# ESP32Board_V1.net
KiCad netlist of a schematic drawn in EAGLE
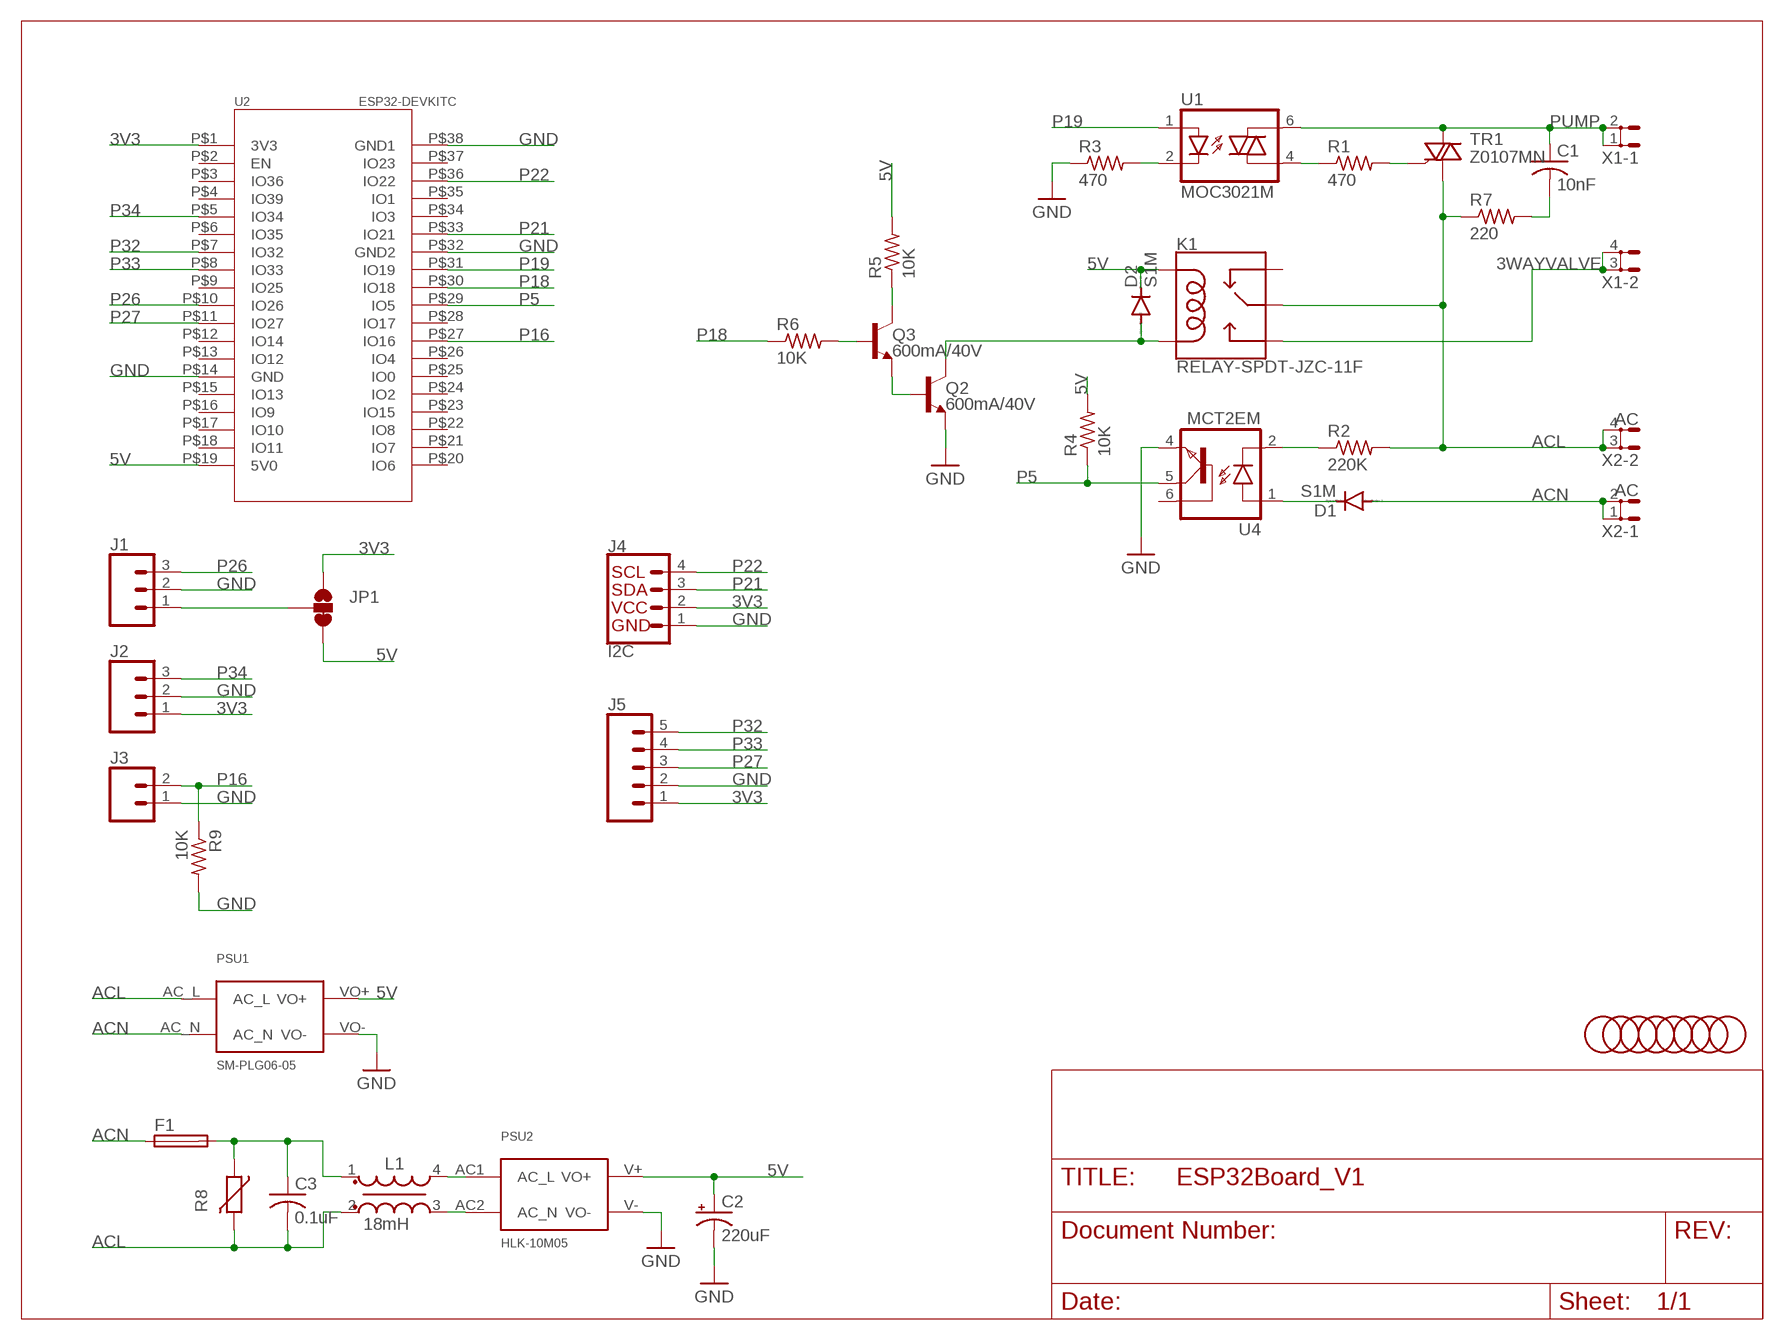
[diagram p0: schematic, sheet 1]

(export (version "E")
  (design (tool "Eeschema 10.0.6"))
  (components
    (comp (ref "C1")
      (value "10nF")
      (footprint "eagle-import:C075-032X103")
      (fields (field (name "BOM_SUPPLIERPART") "C506848"))
      (libsource (lib "eagle-import") (part "C-US075-032X103"))
    )
    (comp (ref "C2")
      (value "220uF")
      (footprint "eagle-import:E2,5-6")
      (libsource (lib "eagle-import") (part "CPOL-USE2.5-6"))
    )
    (comp (ref "C3")
      (value "0.1uF")
      (footprint "eagle-import:C150-054X183")
      (libsource (lib "eagle-import") (part "C-US150-054X183"))
    )
    (comp (ref "D1")
      (value "S1M")
      (footprint "eagle-import:SMA")
      (fields (field (name "BOM_SUPPLIERPART") "C232826"))
      (libsource (lib "eagle-import") (part "S1M"))
    )
    (comp (ref "D2")
      (value "S1M")
      (footprint "eagle-import:SMA")
      (fields (field (name "BOM_SUPPLIERPART") "C232826"))
      (libsource (lib "eagle-import") (part "S1M"))
    )
    (comp (ref "F1")
      (value "FUSETE5")
      (footprint "eagle-import:TE5")
      (libsource (lib "eagle-import") (part "FUSETE5"))
    )
    (comp (ref "J1")
      (value "CONN_03JST-PTH")
      (footprint "eagle-import:JST-3-PTH")
      (fields (field (name "BOM_SUPPLIERPART") "C157929"))
      (libsource (lib "eagle-import") (part "CONN_03JST-PTH"))
    )
    (comp (ref "J2")
      (value "CONN_03JST-PTH")
      (footprint "eagle-import:JST-3-PTH")
      (fields (field (name "BOM_SUPPLIERPART") "C157929"))
      (libsource (lib "eagle-import") (part "CONN_03JST-PTH"))
    )
    (comp (ref "J3")
      (value "CONN_02JST-PTH-2")
      (footprint "eagle-import:JST-2-PTH")
      (fields (field (name "BOM_SUPPLIERPART") "C173752"))
      (libsource (lib "eagle-import") (part "CONN_02JST-PTH-2"))
    )
    (comp (ref "J4")
      (value "I2C")
      (footprint "eagle-import:JST04_1MM_VERT")
      (fields (field (name "BOM_SUPPLIERPART") "C160390"))
      (libsource (lib "eagle-import") (part "QWIIC_CONNECTOR"))
    )
    (comp (ref "J5")
      (value "CONN_05JST")
      (footprint "eagle-import:JST-5-PTH")
      (fields (field (name "BOM_SUPPLIERPART") "C157923"))
      (libsource (lib "eagle-import") (part "CONN_05JST"))
    )
    (comp (ref "JP1")
      (value "JUMPER-SMT_3_1-NC_TRACE_SILK")
      (footprint "eagle-import:SMT-JUMPER_3_1-NC_TRACE_SILK")
      (libsource (lib "eagle-import") (part "JUMPER-SMT_3_1-NC_TRACE_SILK"))
    )
    (comp (ref "K1")
      (value "RELAY-SPDT-JZC-11F")
      (footprint "eagle-import:RELAY-JZC")
      (fields (field (name "BOM_SUPPLIERPART") "C355393"))
      (libsource (lib "eagle-import") (part "RELAY-SPDT-JZC-11F"))
    )
    (comp (ref "L1")
      (value "18mH")
      (footprint "eagle-import:WE-TFC_UU9.8V")
      (libsource (lib "eagle-import") (part "WE-TFC_UU9.8V_744862180"))
    )
    (comp (ref "PSU1")
      (value "SM-PLG06-05")
      (footprint "eagle-import:SM-PLG06")
      (libsource (lib "eagle-import") (part "SM-PLG06-05"))
    )
    (comp (ref "PSU2")
      (value "HLK-10M05")
      (footprint "eagle-import:HLK-10MXX")
      (libsource (lib "eagle-import") (part "HLK-10M05"))
    )
    (comp (ref "Q2")
      (value "600mA/40V")
      (footprint "eagle-import:SOT23-3")
      (fields (field (name "BOM_SUPPLIERPART") "C164886"))
      (libsource (lib "eagle-import") (part "TRANS_NPN-MMBT2222AL"))
    )
    (comp (ref "Q3")
      (value "600mA/40V")
      (footprint "eagle-import:SOT23-3")
      (fields (field (name "BOM_SUPPLIERPART") "C164886"))
      (libsource (lib "eagle-import") (part "TRANS_NPN-MMBT2222AL"))
    )
    (comp (ref "R1")
      (value "470")
      (footprint "eagle-import:R0603")
      (fields (field (name "BOM_SUPPLIERPART") "C328361"))
      (libsource (lib "eagle-import") (part "R-US_R0603"))
    )
    (comp (ref "R2")
      (value "220K")
      (footprint "eagle-import:R0603")
      (fields (field (name "BOM_SUPPLIERPART") "C217882"))
      (libsource (lib "eagle-import") (part "R-US_R0603"))
    )
    (comp (ref "R3")
      (value "470")
      (footprint "eagle-import:R0603")
      (fields (field (name "BOM_SUPPLIERPART") "C328361"))
      (libsource (lib "eagle-import") (part "R-US_R0603"))
    )
    (comp (ref "R4")
      (value "10K")
      (footprint "eagle-import:R0603")
      (fields (field (name "BOM_SUPPLIERPART") "C319939"))
      (libsource (lib "eagle-import") (part "R-US_R0603"))
    )
    (comp (ref "R5")
      (value "10K")
      (footprint "eagle-import:R0603")
      (fields (field (name "BOM_SUPPLIERPART") "C319939"))
      (libsource (lib "eagle-import") (part "R-US_R0603"))
    )
    (comp (ref "R6")
      (value "10K")
      (footprint "eagle-import:R0603")
      (fields (field (name "BOM_SUPPLIERPART") "C319939"))
      (libsource (lib "eagle-import") (part "R-US_R0603"))
    )
    (comp (ref "R7")
      (value "220")
      (footprint "eagle-import:R2512")
      (fields (field (name "BOM_SUPPLIERPART") "C416197"))
      (libsource (lib "eagle-import") (part "R-US_R2512"))
    )
    (comp (ref "R8")
      (value "VARISTOR-7,5")
      (footprint "eagle-import:R-7,5")
      (libsource (lib "eagle-import") (part "VARISTOR-7,5"))
    )
    (comp (ref "R9")
      (value "10K")
      (footprint "eagle-import:R0603")
      (fields (field (name "BOM_SUPPLIERPART") "C319939"))
      (libsource (lib "eagle-import") (part "R-US_R0603"))
    )
    (comp (ref "TR1")
      (value "Z0107MN")
      (footprint "eagle-import:SOT223")
      (fields (field (name "BOM_SUPPLIERPART") "C71218"))
      (libsource (lib "eagle-import") (part "Z0107MNSOT-223"))
    )
    (comp (ref "U$1")
      (value "FIDUCIAL")
      (footprint "eagle-import:FIDUCIAL_1MM")
      (libsource (lib "eagle-import") (part "FIDUCIAL"))
    )
    (comp (ref "U$2")
      (value "FIDUCIAL")
      (footprint "eagle-import:FIDUCIAL_1MM")
      (libsource (lib "eagle-import") (part "FIDUCIAL"))
    )
    (comp (ref "U$3")
      (value "FIDUCIAL")
      (footprint "eagle-import:FIDUCIAL_1MM")
      (libsource (lib "eagle-import") (part "FIDUCIAL"))
    )
    (comp (ref "U$4")
      (value "FIDUCIAL")
      (footprint "eagle-import:FIDUCIAL_1MM")
      (libsource (lib "eagle-import") (part "FIDUCIAL"))
    )
    (comp (ref "U$5")
      (value "FIDUCIAL")
      (footprint "eagle-import:FIDUCIAL_1MM")
      (libsource (lib "eagle-import") (part "FIDUCIAL"))
    )
    (comp (ref "U$6")
      (value "FIDUCIAL")
      (footprint "eagle-import:FIDUCIAL_1MM")
      (libsource (lib "eagle-import") (part "FIDUCIAL"))
    )
    (comp (ref "U$7")
      (value "FIDUCIAL")
      (footprint "eagle-import:FIDUCIAL_1MM")
      (libsource (lib "eagle-import") (part "FIDUCIAL"))
    )
    (comp (ref "U$8")
      (value "FIDUCIAL")
      (footprint "eagle-import:FIDUCIAL_1MM")
      (libsource (lib "eagle-import") (part "FIDUCIAL"))
    )
    (comp (ref "U1")
      (value "MOC3021M")
      (footprint "eagle-import:DIL06")
      (fields (field (name "BOM_SUPPLIERPART") "C5242"))
      (libsource (lib "eagle-import") (part "MOC3021M"))
    )
    (comp (ref "U2")
      (value "ESP32-DEVKITC")
      (footprint "eagle-import:ESP32-DEVKITC")
      (libsource (lib "eagle-import") (part "ESP32-DEVKITC"))
    )
    (comp (ref "U4")
      (value "MCT2EM")
      (footprint "eagle-import:PDIP6_8P89X6P60_ONS")
      (fields
        (field (name "BOM_SUPPLIERPART") "C258259")
        (field (name "COPYRIGHT") "Copyright (C) 2021 Ultra Librarian. All rights reserved.")
      )
      (libsource (lib "eagle-import") (part "MCT2EM"))
    )
    (comp (ref "X1")
      (value "SH5-2")
      (footprint "eagle-import:SH5-2")
      (fields (field (name "BOM_SUPPLIERPART") "C305817"))
      (libsource (lib "eagle-import") (part "SH5-2"))
    )
    (comp (ref "X2")
      (value "AC")
      (footprint "eagle-import:SH5-2")
      (fields (field (name "BOM_SUPPLIERPART") "C305817"))
      (libsource (lib "eagle-import") (part "SH5-2"))
    )
  )
  (nets
    (net (code "1") (name "/3V3") (class "Default")
      (node (ref "J2") (pin "1") (pinfunction "1_1") (pintype "passive"))
      (node (ref "J4") (pin "2") (pinfunction "2_2") (pintype "power_in"))
      (node (ref "J5") (pin "1") (pinfunction "1_1") (pintype "passive"))
      (node (ref "JP1") (pin "1") (pinfunction "1_1") (pintype "passive"))
      (node (ref "U2") (pin "P$1") (pinfunction "3V3_P$1") (pintype "bidirectional"))
    )
    (net (code "2") (name "/3WAYVALVE") (class "Default")
      (node (ref "K1") (pin "3") (pinfunction "NO_3") (pintype "bidirectional"))
      (node (ref "X1") (pin "3") (pinfunction "1_3") (pintype "passive"))
      (node (ref "X1") (pin "4") (pinfunction "2_4") (pintype "passive"))
    )
    (net (code "3") (name "/5V") (class "Default")
      (node (ref "C2") (pin "+") (pinfunction "+_+") (pintype "passive"))
      (node (ref "D2") (pin "C") (pinfunction "C_C") (pintype "passive"))
      (node (ref "JP1") (pin "3") (pinfunction "3_3") (pintype "passive"))
      (node (ref "K1") (pin "5") (pinfunction "COIL1_5") (pintype "bidirectional"))
      (node (ref "PSU1") (pin "VO+") (pinfunction "VO+_VO+") (pintype "bidirectional"))
      (node (ref "PSU2") (pin "V+") (pinfunction "VO+_V+") (pintype "bidirectional"))
      (node (ref "R4") (pin "2") (pinfunction "2_2") (pintype "passive"))
      (node (ref "R5") (pin "2") (pinfunction "2_2") (pintype "passive"))
      (node (ref "U2") (pin "P$19") (pinfunction "5V0_P$19") (pintype "bidirectional"))
    )
    (net (code "4") (name "/ACL") (class "Default")
      (node (ref "C3") (pin "2") (pinfunction "2_2") (pintype "passive"))
      (node (ref "K1") (pin "4") (pinfunction "MAIN_4") (pintype "bidirectional"))
      (node (ref "L1") (pin "2") (pinfunction "2_2") (pintype "passive"))
      (node (ref "PSU1") (pin "AC_L") (pinfunction "AC_L_AC_L") (pintype "bidirectional"))
      (node (ref "R2") (pin "2") (pinfunction "2_2") (pintype "passive"))
      (node (ref "R7") (pin "1") (pinfunction "1_1") (pintype "passive"))
      (node (ref "R8") (pin "2") (pinfunction "2_2") (pintype "passive"))
      (node (ref "TR1") (pin "1") (pinfunction "A1_1") (pintype "passive"))
      (node (ref "X2") (pin "3") (pinfunction "1_3") (pintype "passive"))
      (node (ref "X2") (pin "4") (pinfunction "2_4") (pintype "passive"))
    )
    (net (code "5") (name "/ACN") (class "Default")
      (node (ref "D1") (pin "A") (pinfunction "A_A") (pintype "passive"))
      (node (ref "F1") (pin "1") (pinfunction "1_1") (pintype "passive"))
      (node (ref "PSU1") (pin "AC_N") (pinfunction "AC_N_AC_N") (pintype "bidirectional"))
      (node (ref "X2") (pin "1") (pinfunction "1_1") (pintype "passive"))
      (node (ref "X2") (pin "2") (pinfunction "2_2") (pintype "passive"))
    )
    (net (code "6") (name "/P5") (class "Default")
      (node (ref "R4") (pin "1") (pinfunction "1_1") (pintype "passive"))
      (node (ref "U2") (pin "P$29") (pinfunction "IO5_P$29") (pintype "bidirectional"))
      (node (ref "U4") (pin "5") (pinfunction "COL_5") (pintype "passive"))
    )
    (net (code "7") (name "/P16") (class "Default")
      (node (ref "J3") (pin "2") (pinfunction "2_2") (pintype "passive"))
      (node (ref "R9") (pin "1") (pinfunction "1_1") (pintype "passive"))
      (node (ref "U2") (pin "P$27") (pinfunction "IO16_P$27") (pintype "bidirectional"))
    )
    (net (code "8") (name "/P18") (class "Default")
      (node (ref "R6") (pin "1") (pinfunction "1_1") (pintype "passive"))
      (node (ref "U2") (pin "P$30") (pinfunction "IO18_P$30") (pintype "bidirectional"))
    )
    (net (code "9") (name "/P19") (class "Default")
      (node (ref "U1") (pin "1") (pinfunction "A_1") (pintype "passive"))
      (node (ref "U2") (pin "P$31") (pinfunction "IO19_P$31") (pintype "bidirectional"))
    )
    (net (code "10") (name "/P21") (class "Default")
      (node (ref "J4") (pin "3") (pinfunction "3_3") (pintype "passive"))
      (node (ref "U2") (pin "P$33") (pinfunction "IO21_P$33") (pintype "bidirectional"))
    )
    (net (code "11") (name "/P22") (class "Default")
      (node (ref "J4") (pin "4") (pinfunction "4_4") (pintype "passive"))
      (node (ref "U2") (pin "P$36") (pinfunction "IO22_P$36") (pintype "bidirectional"))
    )
    (net (code "12") (name "/P26") (class "Default")
      (node (ref "J1") (pin "3") (pinfunction "3_3") (pintype "passive"))
      (node (ref "U2") (pin "P$10") (pinfunction "IO26_P$10") (pintype "bidirectional"))
    )
    (net (code "13") (name "/P27") (class "Default")
      (node (ref "J5") (pin "3") (pinfunction "3_3") (pintype "passive"))
      (node (ref "U2") (pin "P$11") (pinfunction "IO27_P$11") (pintype "bidirectional"))
    )
    (net (code "14") (name "/P32") (class "Default")
      (node (ref "J5") (pin "5") (pinfunction "5_5") (pintype "passive"))
      (node (ref "U2") (pin "P$7") (pinfunction "IO32_P$7") (pintype "bidirectional"))
    )
    (net (code "15") (name "/P33") (class "Default")
      (node (ref "J5") (pin "4") (pinfunction "4_4") (pintype "passive"))
      (node (ref "U2") (pin "P$8") (pinfunction "IO33_P$8") (pintype "bidirectional"))
    )
    (net (code "16") (name "/P34") (class "Default")
      (node (ref "J2") (pin "3") (pinfunction "3_3") (pintype "passive"))
      (node (ref "U2") (pin "P$5") (pinfunction "IO34_P$5") (pintype "bidirectional"))
    )
    (net (code "17") (name "/PUMP") (class "Default")
      (node (ref "C1") (pin "1") (pinfunction "1_1") (pintype "passive"))
      (node (ref "TR1") (pin "2") (pinfunction "A2_2") (pintype "passive"))
      (node (ref "TR1") (pin "4") (pinfunction "A2_4") (pintype "passive"))
      (node (ref "U1") (pin "6") (pinfunction "A2_6") (pintype "passive"))
      (node (ref "X1") (pin "1") (pinfunction "1_1") (pintype "passive"))
      (node (ref "X1") (pin "2") (pinfunction "2_2") (pintype "passive"))
    )
    (net (code "18") (name "GND") (class "Default")
      (node (ref "C2") (pin "-") (pinfunction "-_-") (pintype "passive"))
      (node (ref "J1") (pin "2") (pinfunction "2_2") (pintype "passive"))
      (node (ref "J2") (pin "2") (pinfunction "2_2") (pintype "passive"))
      (node (ref "J3") (pin "1") (pinfunction "1_1") (pintype "passive"))
      (node (ref "J4") (pin "1") (pinfunction "1_1") (pintype "power_in"))
      (node (ref "J5") (pin "2") (pinfunction "2_2") (pintype "passive"))
      (node (ref "PSU1") (pin "VO-") (pinfunction "VO-_VO-") (pintype "bidirectional"))
      (node (ref "PSU2") (pin "V-") (pinfunction "VO-_V-") (pintype "bidirectional"))
      (node (ref "Q2") (pin "2") (pinfunction "E_2") (pintype "passive"))
      (node (ref "R3") (pin "1") (pinfunction "1_1") (pintype "passive"))
      (node (ref "R9") (pin "2") (pinfunction "2_2") (pintype "passive"))
      (node (ref "U2") (pin "P$14") (pinfunction "GND_P$14") (pintype "bidirectional"))
      (node (ref "U2") (pin "P$32") (pinfunction "GND2_P$32") (pintype "bidirectional"))
      (node (ref "U2") (pin "P$38") (pinfunction "GND1_P$38") (pintype "bidirectional"))
      (node (ref "U4") (pin "4") (pinfunction "EMI_4") (pintype "passive"))
    )
    (net (code "19") (name "Net-(C1-Pad2)") (class "Default")
      (node (ref "C1") (pin "2") (pinfunction "2_2") (pintype "passive"))
      (node (ref "R7") (pin "2") (pinfunction "2_2") (pintype "passive"))
    )
    (net (code "20") (name "Net-(C3-Pad1)") (class "Default")
      (node (ref "C3") (pin "1") (pinfunction "1_1") (pintype "passive"))
      (node (ref "F1") (pin "2") (pinfunction "2_2") (pintype "passive"))
      (node (ref "L1") (pin "1") (pinfunction "1_1") (pintype "passive"))
      (node (ref "R8") (pin "1") (pinfunction "1_1") (pintype "passive"))
    )
    (net (code "21") (name "Net-(J1-Pad1)") (class "Default")
      (node (ref "J1") (pin "1") (pinfunction "1_1") (pintype "passive"))
      (node (ref "JP1") (pin "2") (pinfunction "2_2") (pintype "passive"))
    )
    (net (code "22") (name "Net-(K1-COIL2)") (class "Default")
      (node (ref "D2") (pin "A") (pinfunction "A_A") (pintype "passive"))
      (node (ref "K1") (pin "1") (pinfunction "COIL2_1") (pintype "bidirectional"))
      (node (ref "Q2") (pin "3") (pinfunction "C_3") (pintype "passive"))
    )
    (net (code "23") (name "Net-(PSU2-AC_L)") (class "Default")
      (node (ref "L1") (pin "4") (pinfunction "4_4") (pintype "passive"))
      (node (ref "PSU2") (pin "AC1") (pinfunction "AC_L_AC1") (pintype "bidirectional"))
    )
    (net (code "24") (name "Net-(PSU2-AC_N)") (class "Default")
      (node (ref "L1") (pin "3") (pinfunction "3_3") (pintype "passive"))
      (node (ref "PSU2") (pin "AC2") (pinfunction "AC_N_AC2") (pintype "bidirectional"))
    )
    (net (code "25") (name "Net-(Q2-B)") (class "Default")
      (node (ref "Q2") (pin "1") (pinfunction "B_1") (pintype "passive"))
      (node (ref "Q3") (pin "2") (pinfunction "E_2") (pintype "passive"))
    )
    (net (code "26") (name "Net-(Q3-B)") (class "Default")
      (node (ref "Q3") (pin "1") (pinfunction "B_1") (pintype "passive"))
      (node (ref "R6") (pin "2") (pinfunction "2_2") (pintype "passive"))
    )
    (net (code "27") (name "Net-(Q3-C)") (class "Default")
      (node (ref "Q3") (pin "3") (pinfunction "C_3") (pintype "passive"))
      (node (ref "R5") (pin "1") (pinfunction "1_1") (pintype "passive"))
    )
    (net (code "28") (name "Net-(TR1-G)") (class "Default")
      (node (ref "R1") (pin "2") (pinfunction "2_2") (pintype "passive"))
      (node (ref "TR1") (pin "3") (pinfunction "G_3") (pintype "passive"))
    )
    (net (code "29") (name "Net-(U1-A1)") (class "Default")
      (node (ref "R1") (pin "1") (pinfunction "1_1") (pintype "passive"))
      (node (ref "U1") (pin "4") (pinfunction "A1_4") (pintype "passive"))
    )
    (net (code "30") (name "Net-(U1-C)") (class "Default")
      (node (ref "R3") (pin "2") (pinfunction "2_2") (pintype "passive"))
      (node (ref "U1") (pin "2") (pinfunction "C_2") (pintype "passive"))
    )
    (net (code "31") (name "Net-(U4-A)") (class "Default")
      (node (ref "D1") (pin "C") (pinfunction "C_C") (pintype "passive"))
      (node (ref "U4") (pin "1") (pinfunction "A_1") (pintype "passive"))
    )
    (net (code "32") (name "Net-(U4-C)") (class "Default")
      (node (ref "R2") (pin "1") (pinfunction "1_1") (pintype "passive"))
      (node (ref "U4") (pin "2") (pinfunction "C_2") (pintype "passive"))
    )
    (net (code "33") (name "unconnected-(K1-NC-Pad2)") (class "Default")
      (node (ref "K1") (pin "2") (pinfunction "NC_2") (pintype "bidirectional"))
    )
    (net (code "34") (name "unconnected-(U2-EN-PadP$2)") (class "Default")
      (node (ref "U2") (pin "P$2") (pinfunction "EN_P$2") (pintype "bidirectional"))
    )
    (net (code "35") (name "unconnected-(U2-IO0-PadP$25)") (class "Default")
      (node (ref "U2") (pin "P$25") (pinfunction "IO0_P$25") (pintype "bidirectional"))
    )
    (net (code "36") (name "unconnected-(U2-IO1-PadP$35)") (class "Default")
      (node (ref "U2") (pin "P$35") (pinfunction "IO1_P$35") (pintype "bidirectional"))
    )
    (net (code "37") (name "unconnected-(U2-IO2-PadP$24)") (class "Default")
      (node (ref "U2") (pin "P$24") (pinfunction "IO2_P$24") (pintype "bidirectional"))
    )
    (net (code "38") (name "unconnected-(U2-IO3-PadP$34)") (class "Default")
      (node (ref "U2") (pin "P$34") (pinfunction "IO3_P$34") (pintype "bidirectional"))
    )
    (net (code "39") (name "unconnected-(U2-IO4-PadP$26)") (class "Default")
      (node (ref "U2") (pin "P$26") (pinfunction "IO4_P$26") (pintype "bidirectional"))
    )
    (net (code "40") (name "unconnected-(U2-IO6-PadP$20)") (class "Default")
      (node (ref "U2") (pin "P$20") (pinfunction "IO6_P$20") (pintype "bidirectional"))
    )
    (net (code "41") (name "unconnected-(U2-IO7-PadP$21)") (class "Default")
      (node (ref "U2") (pin "P$21") (pinfunction "IO7_P$21") (pintype "bidirectional"))
    )
    (net (code "42") (name "unconnected-(U2-IO8-PadP$22)") (class "Default")
      (node (ref "U2") (pin "P$22") (pinfunction "IO8_P$22") (pintype "bidirectional"))
    )
    (net (code "43") (name "unconnected-(U2-IO9-PadP$16)") (class "Default")
      (node (ref "U2") (pin "P$16") (pinfunction "IO9_P$16") (pintype "bidirectional"))
    )
    (net (code "44") (name "unconnected-(U2-IO10-PadP$17)") (class "Default")
      (node (ref "U2") (pin "P$17") (pinfunction "IO10_P$17") (pintype "bidirectional"))
    )
    (net (code "45") (name "unconnected-(U2-IO11-PadP$18)") (class "Default")
      (node (ref "U2") (pin "P$18") (pinfunction "IO11_P$18") (pintype "bidirectional"))
    )
    (net (code "46") (name "unconnected-(U2-IO12-PadP$13)") (class "Default")
      (node (ref "U2") (pin "P$13") (pinfunction "IO12_P$13") (pintype "bidirectional"))
    )
    (net (code "47") (name "unconnected-(U2-IO13-PadP$15)") (class "Default")
      (node (ref "U2") (pin "P$15") (pinfunction "IO13_P$15") (pintype "bidirectional"))
    )
    (net (code "48") (name "unconnected-(U2-IO14-PadP$12)") (class "Default")
      (node (ref "U2") (pin "P$12") (pinfunction "IO14_P$12") (pintype "bidirectional"))
    )
    (net (code "49") (name "unconnected-(U2-IO15-PadP$23)") (class "Default")
      (node (ref "U2") (pin "P$23") (pinfunction "IO15_P$23") (pintype "bidirectional"))
    )
    (net (code "50") (name "unconnected-(U2-IO17-PadP$28)") (class "Default")
      (node (ref "U2") (pin "P$28") (pinfunction "IO17_P$28") (pintype "bidirectional"))
    )
    (net (code "51") (name "unconnected-(U2-IO23-PadP$37)") (class "Default")
      (node (ref "U2") (pin "P$37") (pinfunction "IO23_P$37") (pintype "bidirectional"))
    )
    (net (code "52") (name "unconnected-(U2-IO25-PadP$9)") (class "Default")
      (node (ref "U2") (pin "P$9") (pinfunction "IO25_P$9") (pintype "bidirectional"))
    )
    (net (code "53") (name "unconnected-(U2-IO35-PadP$6)") (class "Default")
      (node (ref "U2") (pin "P$6") (pinfunction "IO35_P$6") (pintype "bidirectional"))
    )
    (net (code "54") (name "unconnected-(U2-IO36-PadP$3)") (class "Default")
      (node (ref "U2") (pin "P$3") (pinfunction "IO36_P$3") (pintype "bidirectional"))
    )
    (net (code "55") (name "unconnected-(U2-IO39-PadP$4)") (class "Default")
      (node (ref "U2") (pin "P$4") (pinfunction "IO39_P$4") (pintype "bidirectional"))
    )
    (net (code "56") (name "unconnected-(U4-BAS-Pad6)") (class "Default")
      (node (ref "U4") (pin "6") (pinfunction "BAS_6") (pintype "passive"))
    )
  )
)
